# power_hv.net
KiCad netlist of a schematic drawn in EAGLE
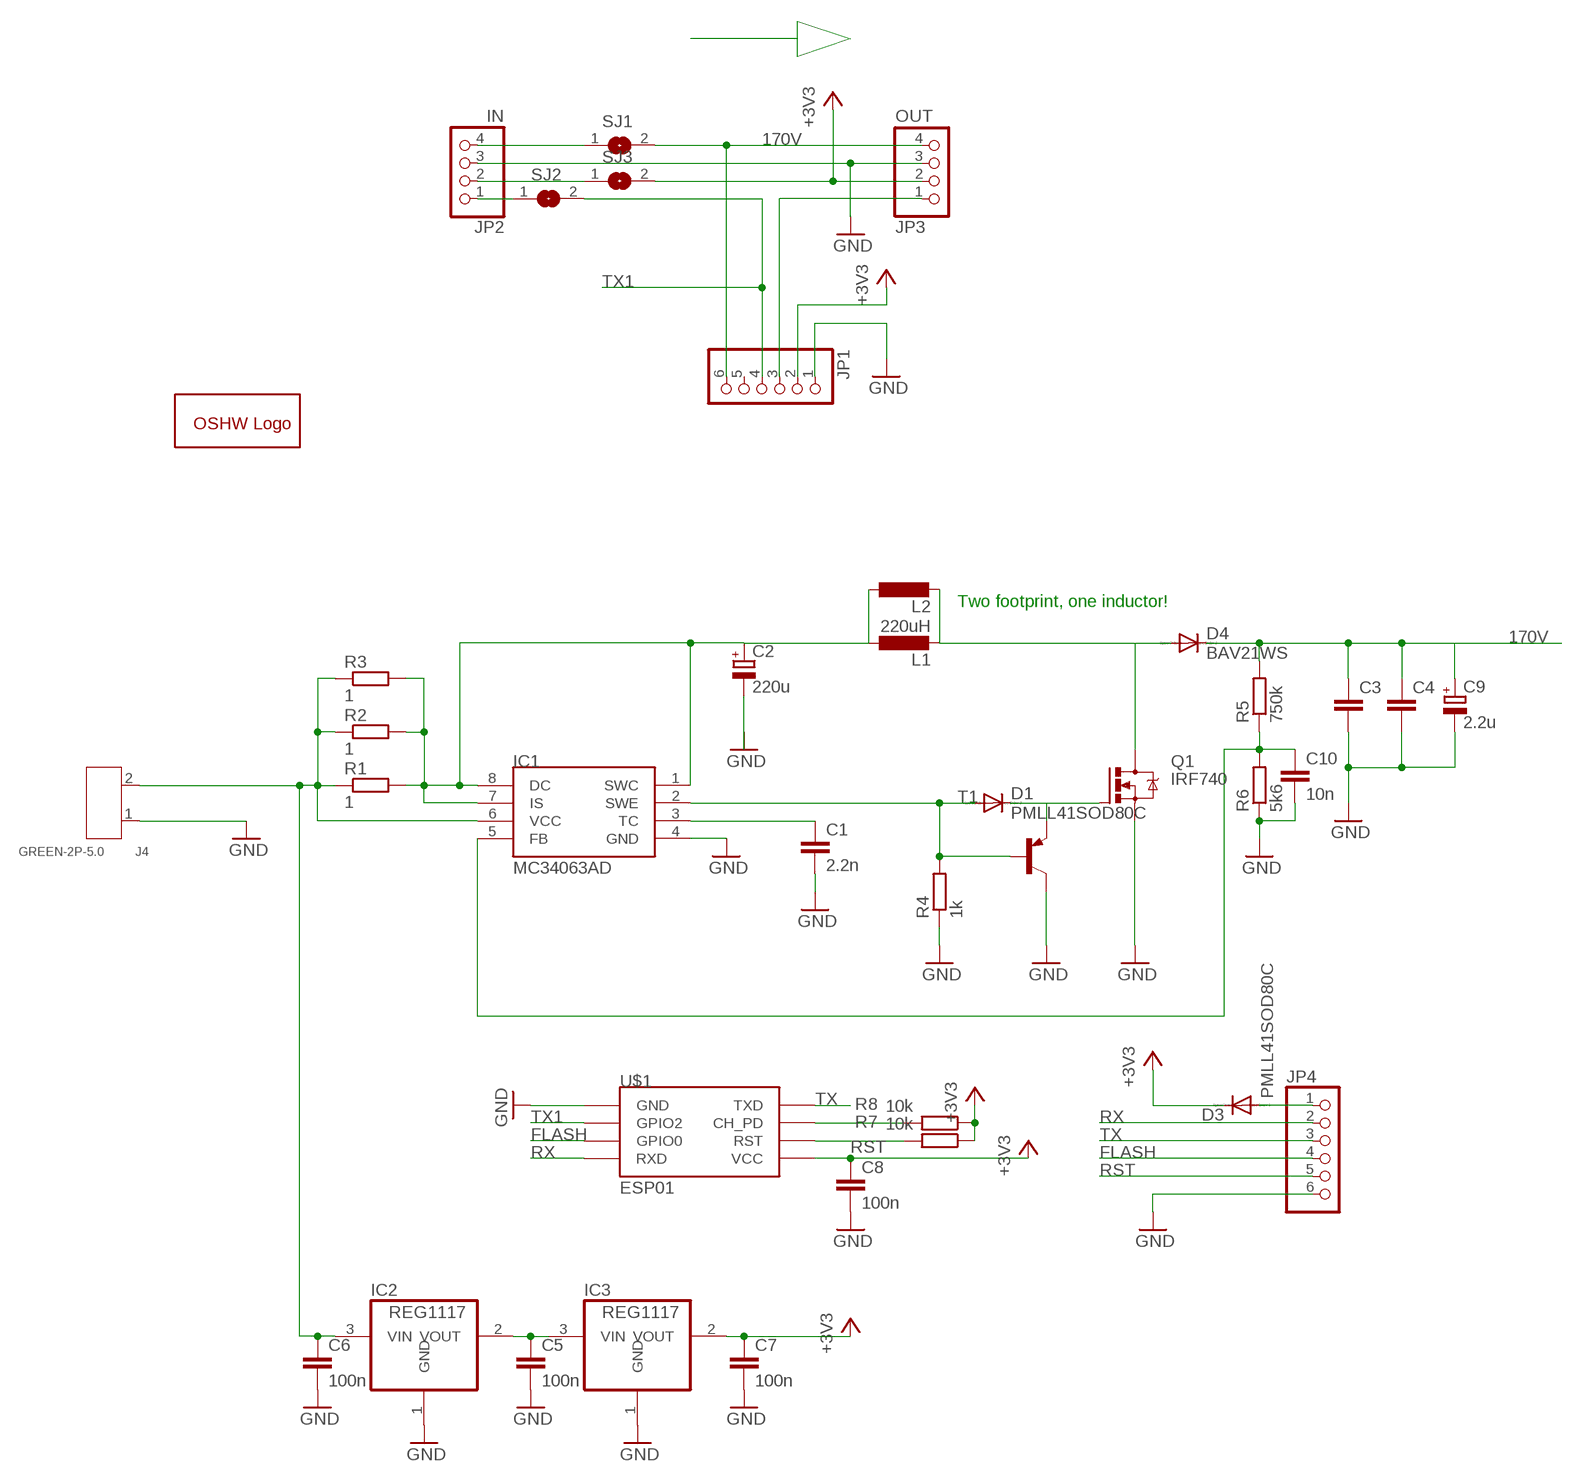
[diagram p0: schematic, sheet 1]

(export (version "E")
  (design (tool "Eeschema 10.0.6"))
  (components
    (comp (ref "C1")
      (value "2.2n")
      (footprint "eagle-import:C0805")
      (libsource (lib "eagle-import") (part "resistor_348_C-EUC0805"))
    )
    (comp (ref "C2")
      (value "220u")
      (footprint "eagle-import:140CLH-0810")
      (libsource (lib "eagle-import") (part "CPOL-EU140CLH-0810"))
    )
    (comp (ref "C3")
      (value "C-EUC1210K")
      (footprint "eagle-import:C1210K")
      (libsource (lib "eagle-import") (part "C-EUC1210K"))
    )
    (comp (ref "C4")
      (value "C-EUC1210K")
      (footprint "eagle-import:C1210K")
      (libsource (lib "eagle-import") (part "C-EUC1210K"))
    )
    (comp (ref "C5")
      (value "100n")
      (footprint "eagle-import:C0805")
      (libsource (lib "eagle-import") (part "resistor_348_C-EUC0805"))
    )
    (comp (ref "C6")
      (value "100n")
      (footprint "eagle-import:C0805")
      (libsource (lib "eagle-import") (part "resistor_348_C-EUC0805"))
    )
    (comp (ref "C7")
      (value "100n")
      (footprint "eagle-import:C0805")
      (libsource (lib "eagle-import") (part "resistor_348_C-EUC0805"))
    )
    (comp (ref "C8")
      (value "100n")
      (footprint "eagle-import:C0805")
      (libsource (lib "eagle-import") (part "resistor_348_C-EUC0805"))
    )
    (comp (ref "C9")
      (value "2.2u")
      (footprint "eagle-import:E5-8,5")
      (libsource (lib "eagle-import") (part "resistor_348_CPOL-EUE5-8.5"))
    )
    (comp (ref "C10")
      (value "10n")
      (footprint "eagle-import:C0805")
      (libsource (lib "eagle-import") (part "resistor_348_C-EUC0805"))
    )
    (comp (ref "D1")
      (value "PMLL41SOD80C")
      (footprint "eagle-import:SOD80C")
      (libsource (lib "eagle-import") (part "PMLL41SOD80C"))
    )
    (comp (ref "D3")
      (value "PMLL41SOD80C")
      (footprint "eagle-import:SOD80C")
      (libsource (lib "eagle-import") (part "PMLL41SOD80C"))
    )
    (comp (ref "D4")
      (value "BAV21WS")
      (footprint "eagle-import:SOD323-W")
      (libsource (lib "eagle-import") (part "DIODE-SOD323-W"))
    )
    (comp (ref "GOLD_ORB_SM1")
      (value "OSHWLOGOLOGO8MM")
      (footprint "eagle-import:OSHW_8MM")
      (libsource (lib "eagle-import") (part "OSHWLOGOLOGO8MM"))
    )
    (comp (ref "IC1")
      (value "MC34063AD")
      (footprint "eagle-import:SOIC8")
      (libsource (lib "eagle-import") (part "MC34063AD"))
    )
    (comp (ref "IC2")
      (value "REG1117")
      (footprint "eagle-import:SOT223")
      (libsource (lib "eagle-import") (part "REG1117"))
    )
    (comp (ref "IC3")
      (value "REG1117")
      (footprint "eagle-import:SOT223")
      (libsource (lib "eagle-import") (part "REG1117"))
    )
    (comp (ref "J4")
      (value "GREEN-2P-5.0")
      (footprint "eagle-import:H2-5.0-10.5X8.0MM")
      (libsource (lib "eagle-import") (part "SCREW-TERMINAL-GREEN(2P-5.0)"))
    )
    (comp (ref "JP1")
      (value "PINHD-1X6")
      (footprint "eagle-import:1X06")
      (libsource (lib "eagle-import") (part "PINHD-1X6"))
    )
    (comp (ref "JP2")
      (value "IN")
      (footprint "eagle-import:1X04")
      (libsource (lib "eagle-import") (part "PINHD-1X4"))
    )
    (comp (ref "JP3")
      (value "OUT")
      (footprint "eagle-import:1X04")
      (libsource (lib "eagle-import") (part "PINHD-1X4"))
    )
    (comp (ref "JP4")
      (value "PINHD-1X6")
      (footprint "eagle-import:1X06")
      (libsource (lib "eagle-import") (part "PINHD-1X6"))
    )
    (comp (ref "L1")
      (value "220uH")
      (footprint "eagle-import:POWER-CHOKE_WE-TPC")
      (libsource (lib "eagle-import") (part "L-EUWE-TPC"))
    )
    (comp (ref "L2")
      (value "L-EU6000-XXX-RC")
      (footprint "eagle-import:6000-XXXX-RC")
      (libsource (lib "eagle-import") (part "L-EU6000-XXX-RC"))
    )
    (comp (ref "Q1")
      (value "IRF740")
      (footprint "eagle-import:TO220BV")
      (libsource (lib "eagle-import") (part "IRF740"))
    )
    (comp (ref "R1")
      (value "1")
      (footprint "eagle-import:R0805")
      (libsource (lib "eagle-import") (part "R-EU_R0805"))
    )
    (comp (ref "R2")
      (value "1")
      (footprint "eagle-import:R0805")
      (libsource (lib "eagle-import") (part "R-EU_R0805"))
    )
    (comp (ref "R3")
      (value "1")
      (footprint "eagle-import:R0805")
      (libsource (lib "eagle-import") (part "R-EU_R0805"))
    )
    (comp (ref "R4")
      (value "1k")
      (footprint "eagle-import:R0805")
      (libsource (lib "eagle-import") (part "R-EU_R0805"))
    )
    (comp (ref "R5")
      (value "750k")
      (footprint "eagle-import:R0805")
      (libsource (lib "eagle-import") (part "R-EU_R0805"))
    )
    (comp (ref "R6")
      (value "5k6")
      (footprint "eagle-import:R0805")
      (libsource (lib "eagle-import") (part "R-EU_R0805"))
    )
    (comp (ref "R7")
      (value "10k")
      (footprint "eagle-import:R0805")
      (libsource (lib "eagle-import") (part "R-EU_R0805"))
    )
    (comp (ref "R8")
      (value "10k")
      (footprint "eagle-import:R0805")
      (libsource (lib "eagle-import") (part "R-EU_R0805"))
    )
    (comp (ref "SJ1") (value "SJ") (footprint "eagle-import:SJ") (libsource (lib "eagle-import") (part "SJ")))
    (comp (ref "SJ2") (value "SJ") (footprint "eagle-import:SJ") (libsource (lib "eagle-import") (part "SJ")))
    (comp (ref "SJ3") (value "SJ") (footprint "eagle-import:SJ") (libsource (lib "eagle-import") (part "SJ")))
    (comp (ref "T1")
      (value "BC807-40-PNP-SOT23-BEC")
      (footprint "eagle-import:SOT23-BEC")
      (libsource (lib "eagle-import") (part "-PNP-SOT23-BECBC807-40"))
    )
    (comp (ref "U$1")
      (value "ESP01")
      (footprint "eagle-import:ESP01")
      (libsource (lib "eagle-import") (part "ESP01"))
    )
  )
  (nets
    (net (code "1") (name "+3V3") (class "Default")
      (node (ref "C7") (pin "1") (pinfunction "1_1") (pintype "passive"))
      (node (ref "C8") (pin "1") (pinfunction "1_1") (pintype "passive"))
      (node (ref "D3") (pin "C") (pinfunction "C_C") (pintype "passive"))
      (node (ref "IC3") (pin "2") (pinfunction "VOUT_2") (pintype "output"))
      (node (ref "JP1") (pin "2") (pinfunction "2_2") (pintype "passive"))
      (node (ref "JP3") (pin "2") (pinfunction "2_2") (pintype "passive"))
      (node (ref "R7") (pin "1") (pinfunction "1_1") (pintype "passive"))
      (node (ref "R8") (pin "1") (pinfunction "1_1") (pintype "passive"))
      (node (ref "SJ3") (pin "2") (pinfunction "2_2") (pintype "passive"))
      (node (ref "U$1") (pin "VCC") (pinfunction "VCC_VCC") (pintype "bidirectional"))
    )
    (net (code "2") (name "/170V") (class "Default")
      (node (ref "C3") (pin "1") (pinfunction "1_1") (pintype "passive"))
      (node (ref "C4") (pin "1") (pinfunction "1_1") (pintype "passive"))
      (node (ref "C9") (pin "+") (pinfunction "+_+") (pintype "passive"))
      (node (ref "D4") (pin "C") (pinfunction "C_C") (pintype "passive"))
      (node (ref "JP1") (pin "6") (pinfunction "6_6") (pintype "passive"))
      (node (ref "JP3") (pin "4") (pinfunction "4_4") (pintype "passive"))
      (node (ref "R5") (pin "2") (pinfunction "2_2") (pintype "passive"))
      (node (ref "SJ1") (pin "2") (pinfunction "2_2") (pintype "passive"))
    )
    (net (code "3") (name "/FLASH") (class "Default")
      (node (ref "JP4") (pin "4") (pinfunction "4_4") (pintype "passive"))
      (node (ref "U$1") (pin "GPIO0") (pinfunction "GPIO0_GPIO0") (pintype "bidirectional"))
    )
    (net (code "4") (name "/RST") (class "Default")
      (node (ref "JP4") (pin "5") (pinfunction "5_5") (pintype "passive"))
      (node (ref "R7") (pin "2") (pinfunction "2_2") (pintype "passive"))
      (node (ref "U$1") (pin "RST") (pinfunction "RST_RST") (pintype "bidirectional"))
    )
    (net (code "5") (name "/RX") (class "Default")
      (node (ref "JP4") (pin "2") (pinfunction "2_2") (pintype "passive"))
      (node (ref "U$1") (pin "RX") (pinfunction "RXD_RX") (pintype "bidirectional"))
    )
    (net (code "6") (name "/TX") (class "Default")
      (node (ref "JP4") (pin "3") (pinfunction "3_3") (pintype "passive"))
      (node (ref "U$1") (pin "TX") (pinfunction "TXD_TX") (pintype "bidirectional"))
    )
    (net (code "7") (name "/TX1") (class "Default")
      (node (ref "JP1") (pin "4") (pinfunction "4_4") (pintype "passive"))
      (node (ref "SJ2") (pin "2") (pinfunction "2_2") (pintype "passive"))
      (node (ref "U$1") (pin "GPIO2") (pinfunction "GPIO2_GPIO2") (pintype "bidirectional"))
    )
    (net (code "8") (name "GND") (class "Default")
      (node (ref "C1") (pin "2") (pinfunction "2_2") (pintype "passive"))
      (node (ref "C10") (pin "2") (pinfunction "2_2") (pintype "passive"))
      (node (ref "C2") (pin "-") (pinfunction "-_-") (pintype "passive"))
      (node (ref "C3") (pin "2") (pinfunction "2_2") (pintype "passive"))
      (node (ref "C4") (pin "2") (pinfunction "2_2") (pintype "passive"))
      (node (ref "C5") (pin "2") (pinfunction "2_2") (pintype "passive"))
      (node (ref "C6") (pin "2") (pinfunction "2_2") (pintype "passive"))
      (node (ref "C7") (pin "2") (pinfunction "2_2") (pintype "passive"))
      (node (ref "C8") (pin "2") (pinfunction "2_2") (pintype "passive"))
      (node (ref "C9") (pin "-") (pinfunction "-_-") (pintype "passive"))
      (node (ref "IC1") (pin "4") (pinfunction "GND_4") (pintype "passive"))
      (node (ref "IC2") (pin "1") (pinfunction "GND_1") (pintype "power_in"))
      (node (ref "IC3") (pin "1") (pinfunction "GND_1") (pintype "power_in"))
      (node (ref "J4") (pin "1") (pinfunction "1_1") (pintype "bidirectional"))
      (node (ref "JP1") (pin "1") (pinfunction "1_1") (pintype "passive"))
      (node (ref "JP2") (pin "3") (pinfunction "3_3") (pintype "passive"))
      (node (ref "JP3") (pin "3") (pinfunction "3_3") (pintype "passive"))
      (node (ref "JP4") (pin "6") (pinfunction "6_6") (pintype "passive"))
      (node (ref "Q1") (pin "S") (pinfunction "S_S") (pintype "passive"))
      (node (ref "R4") (pin "1") (pinfunction "1_1") (pintype "passive"))
      (node (ref "R6") (pin "1") (pinfunction "1_1") (pintype "passive"))
      (node (ref "T1") (pin "C") (pinfunction "C_C") (pintype "passive"))
      (node (ref "U$1") (pin "GND") (pinfunction "GND_GND") (pintype "bidirectional"))
    )
    (net (code "9") (name "Net-(D1-PadC)") (class "Default")
      (node (ref "D1") (pin "C") (pinfunction "C_C") (pintype "passive"))
      (node (ref "Q1") (pin "G") (pinfunction "G_G") (pintype "passive"))
      (node (ref "T1") (pin "E") (pinfunction "E_E") (pintype "passive"))
    )
    (net (code "10") (name "Net-(D3-PadA)") (class "Default")
      (node (ref "D3") (pin "A") (pinfunction "A_A") (pintype "passive"))
      (node (ref "JP4") (pin "1") (pinfunction "1_1") (pintype "passive"))
    )
    (net (code "11") (name "Net-(D4-PadA)") (class "Default")
      (node (ref "D4") (pin "A") (pinfunction "A_A") (pintype "passive"))
      (node (ref "L1") (pin "2") (pinfunction "2_2") (pintype "passive"))
      (node (ref "L2") (pin "2") (pinfunction "2_2") (pintype "passive"))
      (node (ref "Q1") (pin "D") (pinfunction "D_D") (pintype "passive"))
    )
    (net (code "12") (name "Net-(IC1-DC)") (class "Default")
      (node (ref "C2") (pin "+") (pinfunction "+_+") (pintype "passive"))
      (node (ref "IC1") (pin "1") (pinfunction "SWC_1") (pintype "passive"))
      (node (ref "IC1") (pin "7") (pinfunction "IS_7") (pintype "passive"))
      (node (ref "IC1") (pin "8") (pinfunction "DC_8") (pintype "passive"))
      (node (ref "L1") (pin "1") (pinfunction "1_1") (pintype "passive"))
      (node (ref "L2") (pin "1") (pinfunction "1_1") (pintype "passive"))
      (node (ref "R1") (pin "2") (pinfunction "2_2") (pintype "passive"))
      (node (ref "R2") (pin "2") (pinfunction "2_2") (pintype "passive"))
      (node (ref "R3") (pin "2") (pinfunction "2_2") (pintype "passive"))
    )
    (net (code "13") (name "Net-(IC1-FB)") (class "Default")
      (node (ref "C10") (pin "1") (pinfunction "1_1") (pintype "passive"))
      (node (ref "IC1") (pin "5") (pinfunction "FB_5") (pintype "passive"))
      (node (ref "R5") (pin "1") (pinfunction "1_1") (pintype "passive"))
      (node (ref "R6") (pin "2") (pinfunction "2_2") (pintype "passive"))
    )
    (net (code "14") (name "Net-(IC1-SWE)") (class "Default")
      (node (ref "D1") (pin "A") (pinfunction "A_A") (pintype "passive"))
      (node (ref "IC1") (pin "2") (pinfunction "SWE_2") (pintype "passive"))
      (node (ref "R4") (pin "2") (pinfunction "2_2") (pintype "passive"))
      (node (ref "T1") (pin "B") (pinfunction "B_B") (pintype "passive"))
    )
    (net (code "15") (name "Net-(IC1-TC)") (class "Default")
      (node (ref "C1") (pin "1") (pinfunction "1_1") (pintype "passive"))
      (node (ref "IC1") (pin "3") (pinfunction "TC_3") (pintype "passive"))
    )
    (net (code "16") (name "Net-(IC1-VCC)") (class "Default")
      (node (ref "C6") (pin "1") (pinfunction "1_1") (pintype "passive"))
      (node (ref "IC1") (pin "6") (pinfunction "VCC_6") (pintype "passive"))
      (node (ref "IC2") (pin "3") (pinfunction "VIN_3") (pintype "input"))
      (node (ref "J4") (pin "2") (pinfunction "2_2") (pintype "bidirectional"))
      (node (ref "R1") (pin "1") (pinfunction "1_1") (pintype "passive"))
      (node (ref "R2") (pin "1") (pinfunction "1_1") (pintype "passive"))
      (node (ref "R3") (pin "1") (pinfunction "1_1") (pintype "passive"))
    )
    (net (code "17") (name "Net-(IC2-VOUT)") (class "Default")
      (node (ref "C5") (pin "1") (pinfunction "1_1") (pintype "passive"))
      (node (ref "IC2") (pin "2") (pinfunction "VOUT_2") (pintype "output"))
      (node (ref "IC3") (pin "3") (pinfunction "VIN_3") (pintype "input"))
    )
    (net (code "18") (name "Net-(JP1-Pad3)") (class "Default")
      (node (ref "JP1") (pin "3") (pinfunction "3_3") (pintype "passive"))
      (node (ref "JP3") (pin "1") (pinfunction "1_1") (pintype "passive"))
    )
    (net (code "19") (name "Net-(JP2-Pad1)") (class "Default")
      (node (ref "JP2") (pin "1") (pinfunction "1_1") (pintype "passive"))
      (node (ref "SJ2") (pin "1") (pinfunction "1_1") (pintype "passive"))
    )
    (net (code "20") (name "Net-(JP2-Pad2)") (class "Default")
      (node (ref "JP2") (pin "2") (pinfunction "2_2") (pintype "passive"))
      (node (ref "SJ3") (pin "1") (pinfunction "1_1") (pintype "passive"))
    )
    (net (code "21") (name "Net-(JP2-Pad4)") (class "Default")
      (node (ref "JP2") (pin "4") (pinfunction "4_4") (pintype "passive"))
      (node (ref "SJ1") (pin "1") (pinfunction "1_1") (pintype "passive"))
    )
    (net (code "22") (name "Net-(R8-Pad2)") (class "Default")
      (node (ref "R8") (pin "2") (pinfunction "2_2") (pintype "passive"))
      (node (ref "U$1") (pin "CH_PD") (pinfunction "CH_PD_CH_PD") (pintype "bidirectional"))
    )
    (net (code "23") (name "unconnected-(JP1-Pad5)") (class "Default")
      (node (ref "JP1") (pin "5") (pinfunction "5_5") (pintype "passive"))
    )
  )
)
